# usb.net
KiCad netlist of a schematic drawn in Altium Designer
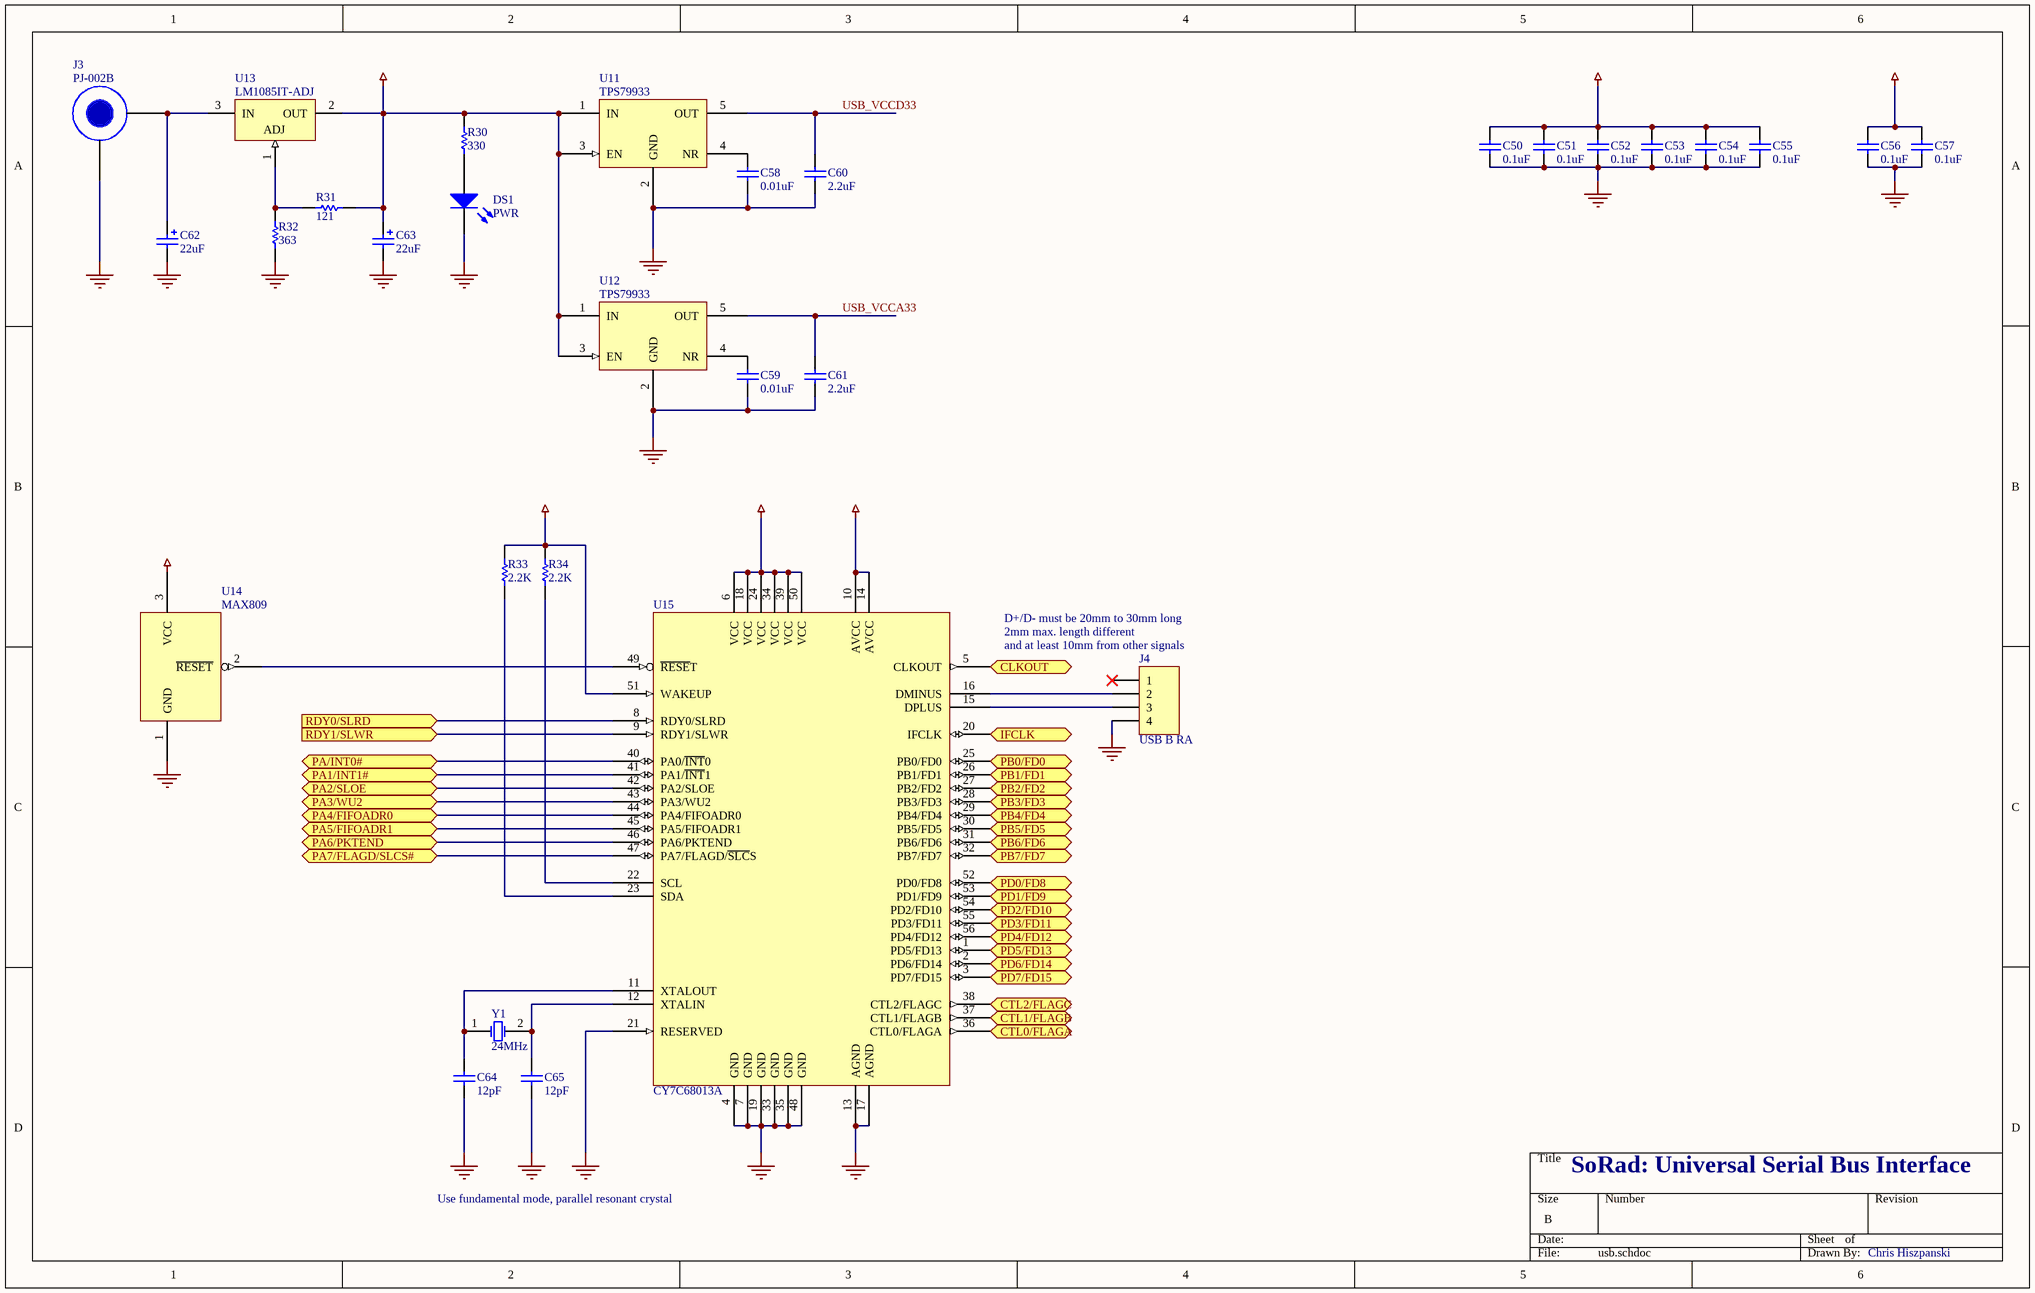
[diagram p0: usb.schdoc]

(export (version "E")
  (design (tool "Eeschema 10.0.6"))
  (components
    (comp (ref "C50")
      (value "0.1uF")
      (footprint "CC2012-0805")
      (description "Capacitor")
      (fields
        (field (name "DISTRIBUTOR PART NUMBER") "PCC1843CT-ND")
        (field (name "MANUFACTURER") "Panasonic")
        (field (name "PUBLISHER") "Altium Limited")
      )
      (libsource (lib "Miscellaneous Devices") (part "Cap"))
    )
    (comp (ref "C51")
      (value "0.1uF")
      (footprint "CC2012-0805")
      (description "Capacitor")
      (fields
        (field (name "DISTRIBUTOR PART NUMBER") "PCC1843CT-ND")
        (field (name "MANUFACTURER") "Panasonic")
        (field (name "PUBLISHER") "Altium Limited")
      )
      (libsource (lib "Miscellaneous Devices") (part "Cap"))
    )
    (comp (ref "C52")
      (value "0.1uF")
      (footprint "CC2012-0805")
      (description "Capacitor")
      (fields
        (field (name "DISTRIBUTOR PART NUMBER") "PCC1843CT-ND")
        (field (name "MANUFACTURER") "Panasonic")
        (field (name "PUBLISHER") "Altium Limited")
      )
      (libsource (lib "Miscellaneous Devices") (part "Cap"))
    )
    (comp (ref "C53")
      (value "0.1uF")
      (footprint "CC2012-0805")
      (description "Capacitor")
      (fields
        (field (name "DISTRIBUTOR PART NUMBER") "PCC1843CT-ND")
        (field (name "MANUFACTURER") "Panasonic")
        (field (name "PUBLISHER") "Altium Limited")
      )
      (libsource (lib "Miscellaneous Devices") (part "Cap"))
    )
    (comp (ref "C54")
      (value "0.1uF")
      (footprint "CC2012-0805")
      (description "Capacitor")
      (fields
        (field (name "DISTRIBUTOR PART NUMBER") "PCC1843CT-ND")
        (field (name "MANUFACTURER") "Panasonic")
        (field (name "PUBLISHER") "Altium Limited")
      )
      (libsource (lib "Miscellaneous Devices") (part "Cap"))
    )
    (comp (ref "C55")
      (value "0.1uF")
      (footprint "CC2012-0805")
      (description "Capacitor")
      (fields
        (field (name "DISTRIBUTOR PART NUMBER") "PCC1843CT-ND")
        (field (name "MANUFACTURER") "Panasonic")
        (field (name "PUBLISHER") "Altium Limited")
      )
      (libsource (lib "Miscellaneous Devices") (part "Cap"))
    )
    (comp (ref "C56")
      (value "0.1uF")
      (footprint "CC2012-0805")
      (description "Capacitor")
      (fields
        (field (name "DISTRIBUTOR PART NUMBER") "PCC1843CT-ND")
        (field (name "MANUFACTURER") "Panasonic")
        (field (name "PUBLISHER") "Altium Limited")
      )
      (libsource (lib "Miscellaneous Devices") (part "Cap"))
    )
    (comp (ref "C57")
      (value "0.1uF")
      (footprint "CC2012-0805")
      (description "Capacitor")
      (fields
        (field (name "DISTRIBUTOR PART NUMBER") "PCC1843CT-ND")
        (field (name "MANUFACTURER") "Panasonic")
        (field (name "PUBLISHER") "Altium Limited")
      )
      (libsource (lib "Miscellaneous Devices") (part "Cap"))
    )
    (comp (ref "C58")
      (value "0.01uF")
      (footprint "CC2012-0805")
      (description "Capacitor")
      (fields
        (field (name "DISTRIBUTOR PART NUMBER") "PCC1858CT-ND")
        (field (name "MANUFACTURER") "Panasonic")
        (field (name "PUBLISHER") "Altium Limited")
      )
      (libsource (lib "Miscellaneous Devices") (part "Cap"))
    )
    (comp (ref "C59")
      (value "0.01uF")
      (footprint "CC2012-0805")
      (description "Capacitor")
      (fields
        (field (name "DISTRIBUTOR PART NUMBER") "PCC1858CT-ND")
        (field (name "MANUFACTURER") "Panasonic")
        (field (name "PUBLISHER") "Altium Limited")
      )
      (libsource (lib "Miscellaneous Devices") (part "Cap"))
    )
    (comp (ref "C60")
      (value "2.2uF")
      (footprint "CC3216-1206")
      (description "Capacitor")
      (fields
        (field (name "DISTRIBUTOR PART NUMBER") "PCC1898CT-ND")
        (field (name "MANUFACTURER") "Panasonic")
        (field (name "PUBLISHER") "Altium Limited")
      )
      (libsource (lib "Miscellaneous Devices") (part "Cap"))
    )
    (comp (ref "C61")
      (value "2.2uF")
      (footprint "CC3216-1206")
      (description "Capacitor")
      (fields
        (field (name "DISTRIBUTOR PART NUMBER") "PCC1898CT-ND")
        (field (name "MANUFACTURER") "Panasonic")
        (field (name "PUBLISHER") "Altium Limited")
      )
      (libsource (lib "Miscellaneous Devices") (part "Cap"))
    )
    (comp (ref "C62")
      (value "22uF")
      (footprint "RB6.3")
      (description "Polarized Capacitor (Radial)")
      (fields
        (field (name "DISTRIBUTOR PART NUMBER") "P837-ND")
        (field (name "MANUFACTURER") "Panasonic")
        (field (name "PUBLISHER") "Altium Limited")
      )
      (libsource (lib "Miscellaneous Devices") (part "Cap Pol1"))
    )
    (comp (ref "C63")
      (value "22uF")
      (footprint "RB6.3")
      (description "Polarized Capacitor (Radial)")
      (fields
        (field (name "DISTRIBUTOR PART NUMBER") "P837-ND")
        (field (name "MANUFACTURER") "Panasonic")
        (field (name "PUBLISHER") "Altium Limited")
      )
      (libsource (lib "Miscellaneous Devices") (part "Cap Pol1"))
    )
    (comp (ref "C64")
      (value "12pF")
      (footprint "CC2012-0805")
      (description "Capacitor")
      (fields
        (field (name "DISTRIBUTOR PART NUMBER") "PCC120CNCT-ND")
        (field (name "MANUFACTURER") "Panasonic")
        (field (name "PUBLISHER") "Altium Limited")
      )
      (libsource (lib "Miscellaneous Devices") (part "Cap"))
    )
    (comp (ref "C65")
      (value "12pF")
      (footprint "CC2012-0805")
      (description "Capacitor")
      (fields
        (field (name "DISTRIBUTOR PART NUMBER") "PCC120CNCT-ND")
        (field (name "MANUFACTURER") "Panasonic")
        (field (name "PUBLISHER") "Altium Limited")
      )
      (libsource (lib "Miscellaneous Devices") (part "Cap"))
    )
    (comp (ref "DS1")
      (value "PWR")
      (footprint "CC2012-0805")
      (description "Typical INFRARED GaAs LED")
      (fields
        (field (name "MANUFACTURER") "Generic Components")
        (field (name "DISTRIBUTOR PART NUMBER") "67-1553-1-ND")
        (field (name "PUBLISHER") "Altium Limited")
      )
      (libsource (lib "Miscellaneous Devices") (part "LED0"))
    )
    (comp (ref "J3")
      (value "PJ-002B")
      (footprint "PJ-002B")
      (description "R/A PCB Mount Power Jack")
      (fields (field (name "DISTRIBUTOR PART NUMBER") "CP-002B-ND") (field (name "MANUFACTURER") "CUI"))
      (libsource (lib "minisdr") (part "PB-002B"))
    )
    (comp (ref "J4")
      (value "USB B RA")
      (footprint "AU-Y1007-R")
      (description "Header, 4-Pin")
      (fields
        (field (name "DISTRIBUTOR PART NUMBER") "AE9925-ND")
        (field (name "MANUFACTURER") "Assmann")
        (field (name "PUBLISHER") "Altium Limited")
      )
      (libsource (lib "Miscellaneous Connectors") (part "Header 4"))
    )
    (comp (ref "R30")
      (value "330")
      (footprint "CR2012-0805")
      (description "Resistor")
      (fields
        (field (name "MANUFACTURER") "Generic Components")
        (field (name "DISTRIBUTOR PART NUMBER") "P330ACT-ND")
        (field (name "PUBLISHER") "Altium Limited")
      )
      (libsource (lib "Miscellaneous Devices") (part "Res1"))
    )
    (comp (ref "R31")
      (value "121")
      (footprint "CC2012-0805")
      (description "Resistor")
      (fields (field (name "MANUFACTURER") "Generic Components") (field (name "PUBLISHER") "Altium Limited"))
      (libsource (lib "Miscellaneous Devices") (part "Res1"))
    )
    (comp (ref "R32")
      (value "363")
      (footprint "CC2012-0805")
      (description "Resistor")
      (fields (field (name "MANUFACTURER") "Generic Components") (field (name "PUBLISHER") "Altium Limited"))
      (libsource (lib "Miscellaneous Devices") (part "Res1"))
    )
    (comp (ref "R33")
      (value "2.2K")
      (footprint "CC2012-0805")
      (description "Resistor")
      (fields
        (field (name "DISTRIBUTOR PART NUMBER") "541-2.20KCCT-ND")
        (field (name "MANUFACTURER") "Vishay/Dale")
        (field (name "PUBLISHER") "Altium Limited")
      )
      (libsource (lib "") (part "Res1_1"))
    )
    (comp (ref "R34")
      (value "2.2K")
      (footprint "CC2012-0805")
      (description "Resistor")
      (fields
        (field (name "DISTRIBUTOR PART NUMBER") "541-2.20KCCT-ND")
        (field (name "MANUFACTURER") "Vishay/Dale")
        (field (name "PUBLISHER") "Altium Limited")
      )
      (libsource (lib "") (part "Res1_1"))
    )
    (comp (ref "U11")
      (value "TPS79933")
      (footprint "SO-G5/P.95")
      (description "LDO Voltage Regulator")
      (fields
        (field (name "DISTRIBUTOR PART NUMBER") "296-17783-1-ND")
        (field (name "MANUFACTURER") "Texas Instruments")
      )
      (libsource (lib "minisdr") (part "TPS799xx"))
    )
    (comp (ref "U12")
      (value "TPS79933")
      (footprint "SO-G5/P.95")
      (description "LDO Voltage Regulator")
      (fields
        (field (name "DISTRIBUTOR PART NUMBER") "296-17783-1-ND")
        (field (name "MANUFACTURER") "Texas Instruments")
      )
      (libsource (lib "minisdr") (part "TPS799xx"))
    )
    (comp (ref "U13")
      (value "LM1085IT-ADJ")
      (footprint "SFM-T3/A4.7V")
      (description "3-Terminal Adjustable Regulator")
      (fields
        (field (name "DISTRIBUTOR PART NUMBER") "LM1085IT-ADJ-ND")
        (field (name "MANUFACTURER") "National Semiconductor")
        (field (name "PUBLISHER") "Altium Limited")
      )
      (libsource (lib "NSC Power Mgt Voltage Regulator") (part "LM317HVT"))
    )
    (comp (ref "U14")
      (value "MAX809")
      (footprint "SOT-23-3")
      (description "POR Supervisory Circuit")
      (fields
        (field (name "DISTRIBUTOR PART NUMBER") "MAX809RTRGOSCT-ND")
        (field (name "MANUFACTURER") "ON Semiconductor")
      )
      (libsource (lib "minisdr") (part "MAX809"))
    )
    (comp (ref "U15")
      (value "CY7C68013A")
      (footprint "SSOP56")
      (description "EZ-USB FX2LP USB Microcontroller (56-SSOP)")
      (fields
        (field (name "DISTRIBUTOR PART NUMBER") "428-1627-ND")
        (field (name "MANUFACTURER") "Cypress Microsystems")
      )
      (libsource (lib "minisdr") (part "CY7C68013A"))
    )
    (comp (ref "Y1")
      (value "24MHz")
      (footprint "HC49US")
      (description "Crystal Oscillator")
      (fields
        (field (name "DISTRIBUTOR PART NUMBER") "XC1005-ND")
        (field (name "MANUFACTURER") "ECS")
        (field (name "PUBLISHER") "Altium Limited")
      )
      (libsource (lib "Miscellaneous Devices") (part "XTAL"))
    )
  )
  (nets
    (net (code "1") (name "/CLKOUT") (class "Default")
      (node (ref "U15") (pin "5") (pinfunction "CLKOUT_5") (pintype "output"))
    )
    (net (code "2") (name "/CTL0{slash}FLAGA") (class "Default")
      (node (ref "U15") (pin "36") (pinfunction "CTL0/FLAGA_36") (pintype "output"))
    )
    (net (code "3") (name "/CTL1{slash}FLAGB") (class "Default")
      (node (ref "U15") (pin "37") (pinfunction "CTL1/FLAGB_37") (pintype "output"))
    )
    (net (code "4") (name "/CTL2{slash}FLAGC") (class "Default")
      (node (ref "U15") (pin "38") (pinfunction "CTL2/FLAGC_38") (pintype "output"))
    )
    (net (code "5") (name "/IFCLK") (class "Default")
      (node (ref "U15") (pin "20") (pinfunction "IFCLK_20") (pintype "bidirectional"))
    )
    (net (code "6") (name "/PA1{slash}INT1#") (class "Default")
      (node (ref "U15") (pin "41") (pinfunction "PA1/~{INT}1_41") (pintype "bidirectional"))
    )
    (net (code "7") (name "/PA2{slash}SLOE") (class "Default")
      (node (ref "U15") (pin "42") (pinfunction "PA2/SLOE_42") (pintype "bidirectional"))
    )
    (net (code "8") (name "/PA3{slash}WU2") (class "Default")
      (node (ref "U15") (pin "43") (pinfunction "PA3/WU2_43") (pintype "bidirectional"))
    )
    (net (code "9") (name "/PA4{slash}FIFOADR0") (class "Default")
      (node (ref "U15") (pin "44") (pinfunction "PA4/FIFOADR0_44") (pintype "bidirectional"))
    )
    (net (code "10") (name "/PA5{slash}FIFOADR1") (class "Default")
      (node (ref "U15") (pin "45") (pinfunction "PA5/FIFOADR1_45") (pintype "bidirectional"))
    )
    (net (code "11") (name "/PA6{slash}PKTEND") (class "Default")
      (node (ref "U15") (pin "46") (pinfunction "PA6/PKTEND_46") (pintype "bidirectional"))
    )
    (net (code "12") (name "/PA7{slash}FLAGD{slash}SLCS#") (class "Default")
      (node (ref "U15") (pin "47") (pinfunction "PA7/FLAGD/~{SLC}S_47") (pintype "bidirectional"))
    )
    (net (code "13") (name "/PA{slash}INT0#") (class "Default")
      (node (ref "U15") (pin "40") (pinfunction "PA0/~{INT}0_40") (pintype "bidirectional"))
    )
    (net (code "14") (name "/PB0{slash}FD0") (class "Default")
      (node (ref "U15") (pin "25") (pinfunction "PB0/FD0_25") (pintype "bidirectional"))
    )
    (net (code "15") (name "/PB1{slash}FD1") (class "Default")
      (node (ref "U15") (pin "26") (pinfunction "PB1/FD1_26") (pintype "bidirectional"))
    )
    (net (code "16") (name "/PB2{slash}FD2") (class "Default")
      (node (ref "U15") (pin "27") (pinfunction "PB2/FD2_27") (pintype "bidirectional"))
    )
    (net (code "17") (name "/PB3{slash}FD3") (class "Default")
      (node (ref "U15") (pin "28") (pinfunction "PB3/FD3_28") (pintype "bidirectional"))
    )
    (net (code "18") (name "/PB4{slash}FD4") (class "Default")
      (node (ref "U15") (pin "29") (pinfunction "PB4/FD4_29") (pintype "bidirectional"))
    )
    (net (code "19") (name "/PB5{slash}FD5") (class "Default")
      (node (ref "U15") (pin "30") (pinfunction "PB5/FD5_30") (pintype "bidirectional"))
    )
    (net (code "20") (name "/PB6{slash}FD6") (class "Default")
      (node (ref "U15") (pin "31") (pinfunction "PB6/FD6_31") (pintype "bidirectional"))
    )
    (net (code "21") (name "/PB7{slash}FD7") (class "Default")
      (node (ref "U15") (pin "32") (pinfunction "PB7/FD7_32") (pintype "bidirectional"))
    )
    (net (code "22") (name "/PD0{slash}FD8") (class "Default")
      (node (ref "U15") (pin "52") (pinfunction "PD0/FD8_52") (pintype "bidirectional"))
    )
    (net (code "23") (name "/PD1{slash}FD9") (class "Default")
      (node (ref "U15") (pin "53") (pinfunction "PD1/FD9_53") (pintype "bidirectional"))
    )
    (net (code "24") (name "/PD2{slash}FD10") (class "Default")
      (node (ref "U15") (pin "54") (pinfunction "PD2/FD10_54") (pintype "bidirectional"))
    )
    (net (code "25") (name "/PD3{slash}FD11") (class "Default")
      (node (ref "U15") (pin "55") (pinfunction "PD3/FD11_55") (pintype "bidirectional"))
    )
    (net (code "26") (name "/PD4{slash}FD12") (class "Default")
      (node (ref "U15") (pin "56") (pinfunction "PD4/FD12_56") (pintype "bidirectional"))
    )
    (net (code "27") (name "/PD5{slash}FD13") (class "Default")
      (node (ref "U15") (pin "1") (pinfunction "PD5/FD13_1") (pintype "bidirectional"))
    )
    (net (code "28") (name "/PD6{slash}FD14") (class "Default")
      (node (ref "U15") (pin "2") (pinfunction "PD6/FD14_2") (pintype "bidirectional"))
    )
    (net (code "29") (name "/PD7{slash}FD15") (class "Default")
      (node (ref "U15") (pin "3") (pinfunction "PD7/FD15_3") (pintype "bidirectional"))
    )
    (net (code "30") (name "/RDY0{slash}SLRD") (class "Default")
      (node (ref "U15") (pin "8") (pinfunction "RDY0/SLRD_8") (pintype "input"))
    )
    (net (code "31") (name "/RDY1{slash}SLWR") (class "Default")
      (node (ref "U15") (pin "9") (pinfunction "RDY1/SLWR_9") (pintype "input"))
    )
    (net (code "32") (name "GND") (class "Default")
      (node (ref "C50") (pin "1") (pinfunction "1_1") (pintype "passive"))
      (node (ref "C51") (pin "1") (pinfunction "1_1") (pintype "passive"))
      (node (ref "C52") (pin "1") (pinfunction "1_1") (pintype "passive"))
      (node (ref "C53") (pin "1") (pinfunction "1_1") (pintype "passive"))
      (node (ref "C54") (pin "1") (pinfunction "1_1") (pintype "passive"))
      (node (ref "C55") (pin "1") (pinfunction "1_1") (pintype "passive"))
      (node (ref "C56") (pin "1") (pinfunction "1_1") (pintype "passive"))
      (node (ref "C57") (pin "1") (pinfunction "1_1") (pintype "passive"))
      (node (ref "C58") (pin "1") (pinfunction "1_1") (pintype "passive"))
      (node (ref "C59") (pin "1") (pinfunction "1_1") (pintype "passive"))
      (node (ref "C60") (pin "1") (pinfunction "1_1") (pintype "passive"))
      (node (ref "C61") (pin "1") (pinfunction "1_1") (pintype "passive"))
      (node (ref "C62") (pin "2") (pinfunction "2_2") (pintype "passive"))
      (node (ref "C63") (pin "2") (pinfunction "2_2") (pintype "passive"))
      (node (ref "C64") (pin "1") (pinfunction "1_1") (pintype "passive"))
      (node (ref "C65") (pin "1") (pinfunction "1_1") (pintype "passive"))
      (node (ref "DS1") (pin "2") (pinfunction "K_2") (pintype "passive"))
      (node (ref "J3") (pin "2") (pinfunction "GND_2") (pintype "power_in"))
      (node (ref "J4") (pin "4") (pinfunction "4_4") (pintype "passive"))
      (node (ref "R32") (pin "1") (pinfunction "1_1") (pintype "passive"))
      (node (ref "U11") (pin "2") (pinfunction "GND_2") (pintype "power_in"))
      (node (ref "U12") (pin "2") (pinfunction "GND_2") (pintype "power_in"))
      (node (ref "U14") (pin "1") (pinfunction "GND_1") (pintype "passive"))
      (node (ref "U15") (pin "13") (pinfunction "AGND_13") (pintype "power_in"))
      (node (ref "U15") (pin "17") (pinfunction "AGND_17") (pintype "power_in"))
      (node (ref "U15") (pin "19") (pinfunction "GND_19") (pintype "power_in"))
      (node (ref "U15") (pin "21") (pinfunction "RESERVED_21") (pintype "input"))
      (node (ref "U15") (pin "33") (pinfunction "GND_33") (pintype "power_in"))
      (node (ref "U15") (pin "35") (pinfunction "GND_35") (pintype "power_in"))
      (node (ref "U15") (pin "4") (pinfunction "GND_4") (pintype "power_in"))
      (node (ref "U15") (pin "48") (pinfunction "GND_48") (pintype "power_in"))
      (node (ref "U15") (pin "7") (pinfunction "GND_7") (pintype "power_in"))
    )
    (net (code "33") (name "Net-(DS1-A)") (class "Default")
      (node (ref "DS1") (pin "1") (pinfunction "A_1") (pintype "passive"))
      (node (ref "R30") (pin "1") (pinfunction "1_1") (pintype "passive"))
    )
    (net (code "34") (name "Net-(J3-VCC)") (class "Default")
      (node (ref "C62") (pin "1") (pinfunction "1_1") (pintype "passive"))
      (node (ref "J3") (pin "1") (pinfunction "VCC_1") (pintype "power_in"))
      (node (ref "U13") (pin "3") (pinfunction "IN_3") (pintype "power_in"))
    )
    (net (code "35") (name "Net-(U11-NR)") (class "Default")
      (node (ref "C58") (pin "2") (pinfunction "2_2") (pintype "passive"))
      (node (ref "U11") (pin "4") (pinfunction "NR_4") (pintype "passive"))
    )
    (net (code "36") (name "Net-(U12-NR)") (class "Default")
      (node (ref "C59") (pin "2") (pinfunction "2_2") (pintype "passive"))
      (node (ref "U12") (pin "4") (pinfunction "NR_4") (pintype "passive"))
    )
    (net (code "37") (name "Net-(U13-ADJ)") (class "Default")
      (node (ref "R31") (pin "1") (pinfunction "1_1") (pintype "passive"))
      (node (ref "R32") (pin "2") (pinfunction "2_2") (pintype "passive"))
      (node (ref "U13") (pin "1") (pinfunction "ADJ_1") (pintype "input"))
    )
    (net (code "38") (name "Net-(U14-~{RESET})") (class "Default")
      (node (ref "U14") (pin "2") (pinfunction "~{RESET}_2") (pintype "output"))
      (node (ref "U15") (pin "49") (pinfunction "~{RESE}T_49") (pintype "input"))
    )
    (net (code "39") (name "Net-(U15-DMINUS)") (class "Default")
      (node (ref "J4") (pin "2") (pinfunction "2_2") (pintype "passive"))
      (node (ref "U15") (pin "16") (pinfunction "DMINUS_16") (pintype "passive"))
    )
    (net (code "40") (name "Net-(U15-DPLUS)") (class "Default")
      (node (ref "J4") (pin "3") (pinfunction "3_3") (pintype "passive"))
      (node (ref "U15") (pin "15") (pinfunction "DPLUS_15") (pintype "passive"))
    )
    (net (code "41") (name "Net-(U15-SCL)") (class "Default")
      (node (ref "R34") (pin "1") (pinfunction "1_1") (pintype "passive"))
      (node (ref "U15") (pin "22") (pinfunction "SCL_22") (pintype "passive"))
    )
    (net (code "42") (name "Net-(U15-SDA)") (class "Default")
      (node (ref "R33") (pin "1") (pinfunction "1_1") (pintype "passive"))
      (node (ref "U15") (pin "23") (pinfunction "SDA_23") (pintype "passive"))
    )
    (net (code "43") (name "Net-(U15-XTALIN)") (class "Default")
      (node (ref "C65") (pin "2") (pinfunction "2_2") (pintype "passive"))
      (node (ref "U15") (pin "12") (pinfunction "XTALIN_12") (pintype "passive"))
      (node (ref "Y1") (pin "2") (pinfunction "OSC2_2") (pintype "passive"))
    )
    (net (code "44") (name "Net-(U15-XTALOUT)") (class "Default")
      (node (ref "C64") (pin "2") (pinfunction "2_2") (pintype "passive"))
      (node (ref "U15") (pin "11") (pinfunction "XTALOUT_11") (pintype "passive"))
      (node (ref "Y1") (pin "1") (pinfunction "OSC1_1") (pintype "passive"))
    )
    (net (code "45") (name "USB_VCCA33") (class "Default")
      (node (ref "C56") (pin "2") (pinfunction "2_2") (pintype "passive"))
      (node (ref "C57") (pin "2") (pinfunction "2_2") (pintype "passive"))
      (node (ref "C61") (pin "2") (pinfunction "2_2") (pintype "passive"))
      (node (ref "U12") (pin "5") (pinfunction "OUT_5") (pintype "power_in"))
      (node (ref "U15") (pin "10") (pinfunction "AVCC_10") (pintype "power_in"))
      (node (ref "U15") (pin "14") (pinfunction "AVCC_14") (pintype "power_in"))
    )
    (net (code "46") (name "USB_VCCD33") (class "Default")
      (node (ref "C50") (pin "2") (pinfunction "2_2") (pintype "passive"))
      (node (ref "C51") (pin "2") (pinfunction "2_2") (pintype "passive"))
      (node (ref "C52") (pin "2") (pinfunction "2_2") (pintype "passive"))
      (node (ref "C53") (pin "2") (pinfunction "2_2") (pintype "passive"))
      (node (ref "C54") (pin "2") (pinfunction "2_2") (pintype "passive"))
      (node (ref "C55") (pin "2") (pinfunction "2_2") (pintype "passive"))
      (node (ref "C60") (pin "2") (pinfunction "2_2") (pintype "passive"))
      (node (ref "R33") (pin "2") (pinfunction "2_2") (pintype "passive"))
      (node (ref "R34") (pin "2") (pinfunction "2_2") (pintype "passive"))
      (node (ref "U11") (pin "5") (pinfunction "OUT_5") (pintype "power_in"))
      (node (ref "U14") (pin "3") (pinfunction "VCC_3") (pintype "power_in"))
      (node (ref "U15") (pin "18") (pinfunction "VCC_18") (pintype "power_in"))
      (node (ref "U15") (pin "24") (pinfunction "VCC_24") (pintype "power_in"))
      (node (ref "U15") (pin "34") (pinfunction "VCC_34") (pintype "power_in"))
      (node (ref "U15") (pin "39") (pinfunction "VCC_39") (pintype "power_in"))
      (node (ref "U15") (pin "50") (pinfunction "VCC_50") (pintype "power_in"))
      (node (ref "U15") (pin "51") (pinfunction "WAKEUP_51") (pintype "input"))
      (node (ref "U15") (pin "6") (pinfunction "VCC_6") (pintype "power_in"))
    )
    (net (code "47") (name "VCC5") (class "Default")
      (node (ref "C63") (pin "1") (pinfunction "1_1") (pintype "passive"))
      (node (ref "R30") (pin "2") (pinfunction "2_2") (pintype "passive"))
      (node (ref "R31") (pin "2") (pinfunction "2_2") (pintype "passive"))
      (node (ref "U11") (pin "1") (pinfunction "IN_1") (pintype "power_in"))
      (node (ref "U11") (pin "3") (pinfunction "EN_3") (pintype "input"))
      (node (ref "U12") (pin "1") (pinfunction "IN_1") (pintype "power_in"))
      (node (ref "U12") (pin "3") (pinfunction "EN_3") (pintype "input"))
      (node (ref "U13") (pin "2") (pinfunction "OUT_2") (pintype "power_in"))
    )
    (net (code "48") (name "unconnected-(J4-Pad1)") (class "Default")
      (node (ref "J4") (pin "1") (pinfunction "1_1") (pintype "passive+no_connect"))
    )
  )
)
